# Isolation.net
KiCad netlist of a schematic drawn in Altium Designer
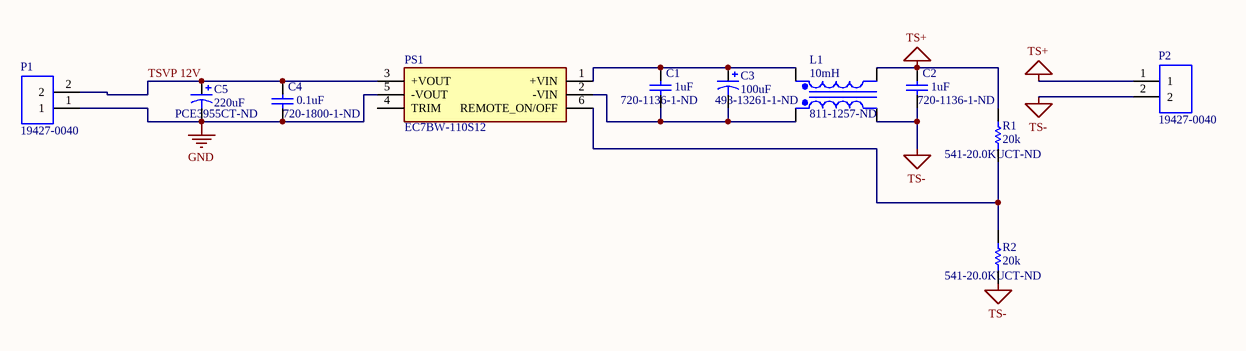
[diagram p0: Isolation.SchDoc]

(export (version "E")
  (design (tool "Eeschema 10.0.6"))
  (components
    (comp (ref "C1")
      (value "1uF")
      (footprint "2225 Package")
      (description "C0603C104K3RACTU")
      (fields
        (field (name "SUPPLIER PART NUMBER 1") "720-1136-1-ND")
        (field (name "Comment") "C0603")
        (field (name "PUBLISHER") "Altium Limited")
      )
      (libsource (lib "Isolation") (part "C0603_1"))
    )
    (comp (ref "C2")
      (value "1uF")
      (footprint "2225 Package")
      (description "C0603C104K3RACTU")
      (fields
        (field (name "SUPPLIER PART NUMBER 1") "720-1136-1-ND")
        (field (name "Comment") "C0603")
        (field (name "PUBLISHER") "Altium Limited")
      )
      (libsource (lib "Isolation") (part "C0603_1"))
    )
    (comp (ref "C3")
      (value "100uF")
      (footprint "NichiconCAP")
      (description "Nichicon 200V 100uF TH Capacitor  UCA2D101MHD6TN")
      (fields (field (name "SUPPLIER PART NUMBER 1") "493-13261-1-ND"))
      (libsource (lib "Isolation") (part "Cap Pol1_1"))
    )
    (comp (ref "C4")
      (value "0.1uF")
      (footprint "C1206")
      (description "C0603C104K3RACTU")
      (fields
        (field (name "SUPPLIER PART NUMBER 1") "720-1800-1-ND")
        (field (name "Comment") "C0603")
        (field (name "PUBLISHER") "Altium Limited")
      )
      (libsource (lib "Isolation") (part "C0603"))
    )
    (comp (ref "C5")
      (value "220uF")
      (footprint "EEE-1VA221UP")
      (description "Panasonic Electrolytic 35V, 20% EEE-1VA221UP")
      (fields (field (name "SUPPLIER PART NUMBER 1") "PCE3955CT-ND"))
      (libsource (lib "Isolation") (part "Cap Pol1"))
    )
    (comp (ref "L1")
      (value "10mH")
      (footprint "52106C")
      (description "MuRata 52106C Common Choke")
      (fields
        (field (name "SUPPLIER PART NUMBER 1") "811-1257-ND")
        (field (name "PUBLISHER") "Altium Limited")
      )
      (libsource (lib "Isolation") (part "Trans Ideal"))
    )
    (comp (ref "P1")
      (value "19427-0040")
      (footprint "MX150L 2pin")
      (description "MX150L 2pin")
      (libsource (lib "Integrated_Library1") (part "19427-0040 MX150L 2pin"))
    )
    (comp (ref "P2")
      (value "19427-0040")
      (footprint "MX150L 2pin")
      (description "MX150L 2pin")
      (libsource (lib "Integrated_Library1") (part "19427-0040 MX150L 2pin"))
    )
    (comp (ref "PS1")
      (value "EC7BW-110S12")
      (footprint "SamacSys:EC7BW110S12")
      (description "Power Supply")
      (fields (field (name "MOUSER PART NUMBER") "418-EC7BW-110S12"))
      (libsource (lib "*") (part "EC7BW-110S12"))
    )
    (comp (ref "R1")
      (value "20k")
      (footprint "C1206")
      (description "Precision Thick Film Chip Resistor, 10 Ohm to 2.2M Ohm Range, 1% Tolerance, 0805 Size, 0.1 W")
      (fields
        (field (name "SUPPLIER PART NUMBER 1") "541-20.0KUCT-ND")
        (field (name "PUBLISHER") "Altium Limited")
      )
      (libsource (lib "Isolation") (part "ERJ6EN"))
    )
    (comp (ref "R2")
      (value "20k")
      (footprint "C1206")
      (description "Precision Thick Film Chip Resistor, 10 Ohm to 2.2M Ohm Range, 1% Tolerance, 0805 Size, 0.1 W")
      (fields
        (field (name "SUPPLIER PART NUMBER 1") "541-20.0KUCT-ND")
        (field (name "PUBLISHER") "Altium Limited")
      )
      (libsource (lib "Isolation") (part "ERJ6EN"))
    )
  )
  (nets
    (net (code "1") (name "/TSVP 12V") (class "Default")
      (node (ref "C4") (pin "2") (pinfunction "2_2") (pintype "passive"))
      (node (ref "C5") (pin "1") (pinfunction "1_1") (pintype "passive"))
      (node (ref "P1") (pin "2") (pinfunction "2_2") (pintype "passive"))
      (node (ref "PS1") (pin "3") (pinfunction "+VOUT_3") (pintype "passive"))
    )
    (net (code "2") (name "GND") (class "Default")
      (node (ref "C4") (pin "1") (pinfunction "1_1") (pintype "passive"))
      (node (ref "C5") (pin "2") (pinfunction "2_2") (pintype "passive"))
      (node (ref "P1") (pin "1") (pinfunction "1_1") (pintype "passive"))
      (node (ref "PS1") (pin "5") (pinfunction "-VOUT_5") (pintype "passive"))
    )
    (net (code "3") (name "Net-(PS1-+VIN)") (class "Default")
      (node (ref "C1") (pin "2") (pinfunction "2_2") (pintype "passive"))
      (node (ref "C3") (pin "1") (pinfunction "1_1") (pintype "passive"))
      (node (ref "L1") (pin "2") (pintype "passive"))
      (node (ref "PS1") (pin "1") (pinfunction "+VIN_1") (pintype "passive"))
    )
    (net (code "4") (name "Net-(PS1--VIN)") (class "Default")
      (node (ref "C1") (pin "1") (pinfunction "1_1") (pintype "passive"))
      (node (ref "C3") (pin "2") (pinfunction "2_2") (pintype "passive"))
      (node (ref "L1") (pin "1") (pintype "passive"))
      (node (ref "PS1") (pin "2") (pinfunction "-VIN_2") (pintype "passive"))
    )
    (net (code "5") (name "Net-(PS1-REMOTE_ON{slash}OFF)") (class "Default")
      (node (ref "PS1") (pin "6") (pinfunction "REMOTE_ON/OFF_6") (pintype "passive"))
      (node (ref "R1") (pin "1") (pinfunction "1_1") (pintype "passive"))
      (node (ref "R2") (pin "2") (pinfunction "2_2") (pintype "passive"))
    )
    (net (code "6") (name "TS+") (class "Default")
      (node (ref "C2") (pin "2") (pinfunction "2_2") (pintype "passive"))
      (node (ref "L1") (pin "3") (pintype "passive"))
      (node (ref "P2") (pin "1") (pinfunction "1_1") (pintype "passive"))
      (node (ref "R1") (pin "2") (pinfunction "2_2") (pintype "passive"))
    )
    (net (code "7") (name "TS-") (class "Default")
      (node (ref "C2") (pin "1") (pinfunction "1_1") (pintype "passive"))
      (node (ref "L1") (pin "4") (pintype "passive"))
      (node (ref "P2") (pin "2") (pinfunction "2_2") (pintype "passive"))
      (node (ref "R2") (pin "1") (pinfunction "1_1") (pintype "passive"))
    )
    (net (code "8") (name "unconnected-(PS1-TRIM-Pad4)") (class "Default")
      (node (ref "PS1") (pin "4") (pinfunction "TRIM_4") (pintype "passive"))
    )
  )
)
